# GSM_Shutter_lock_system.net
KiCad netlist of a schematic drawn in Altium Designer
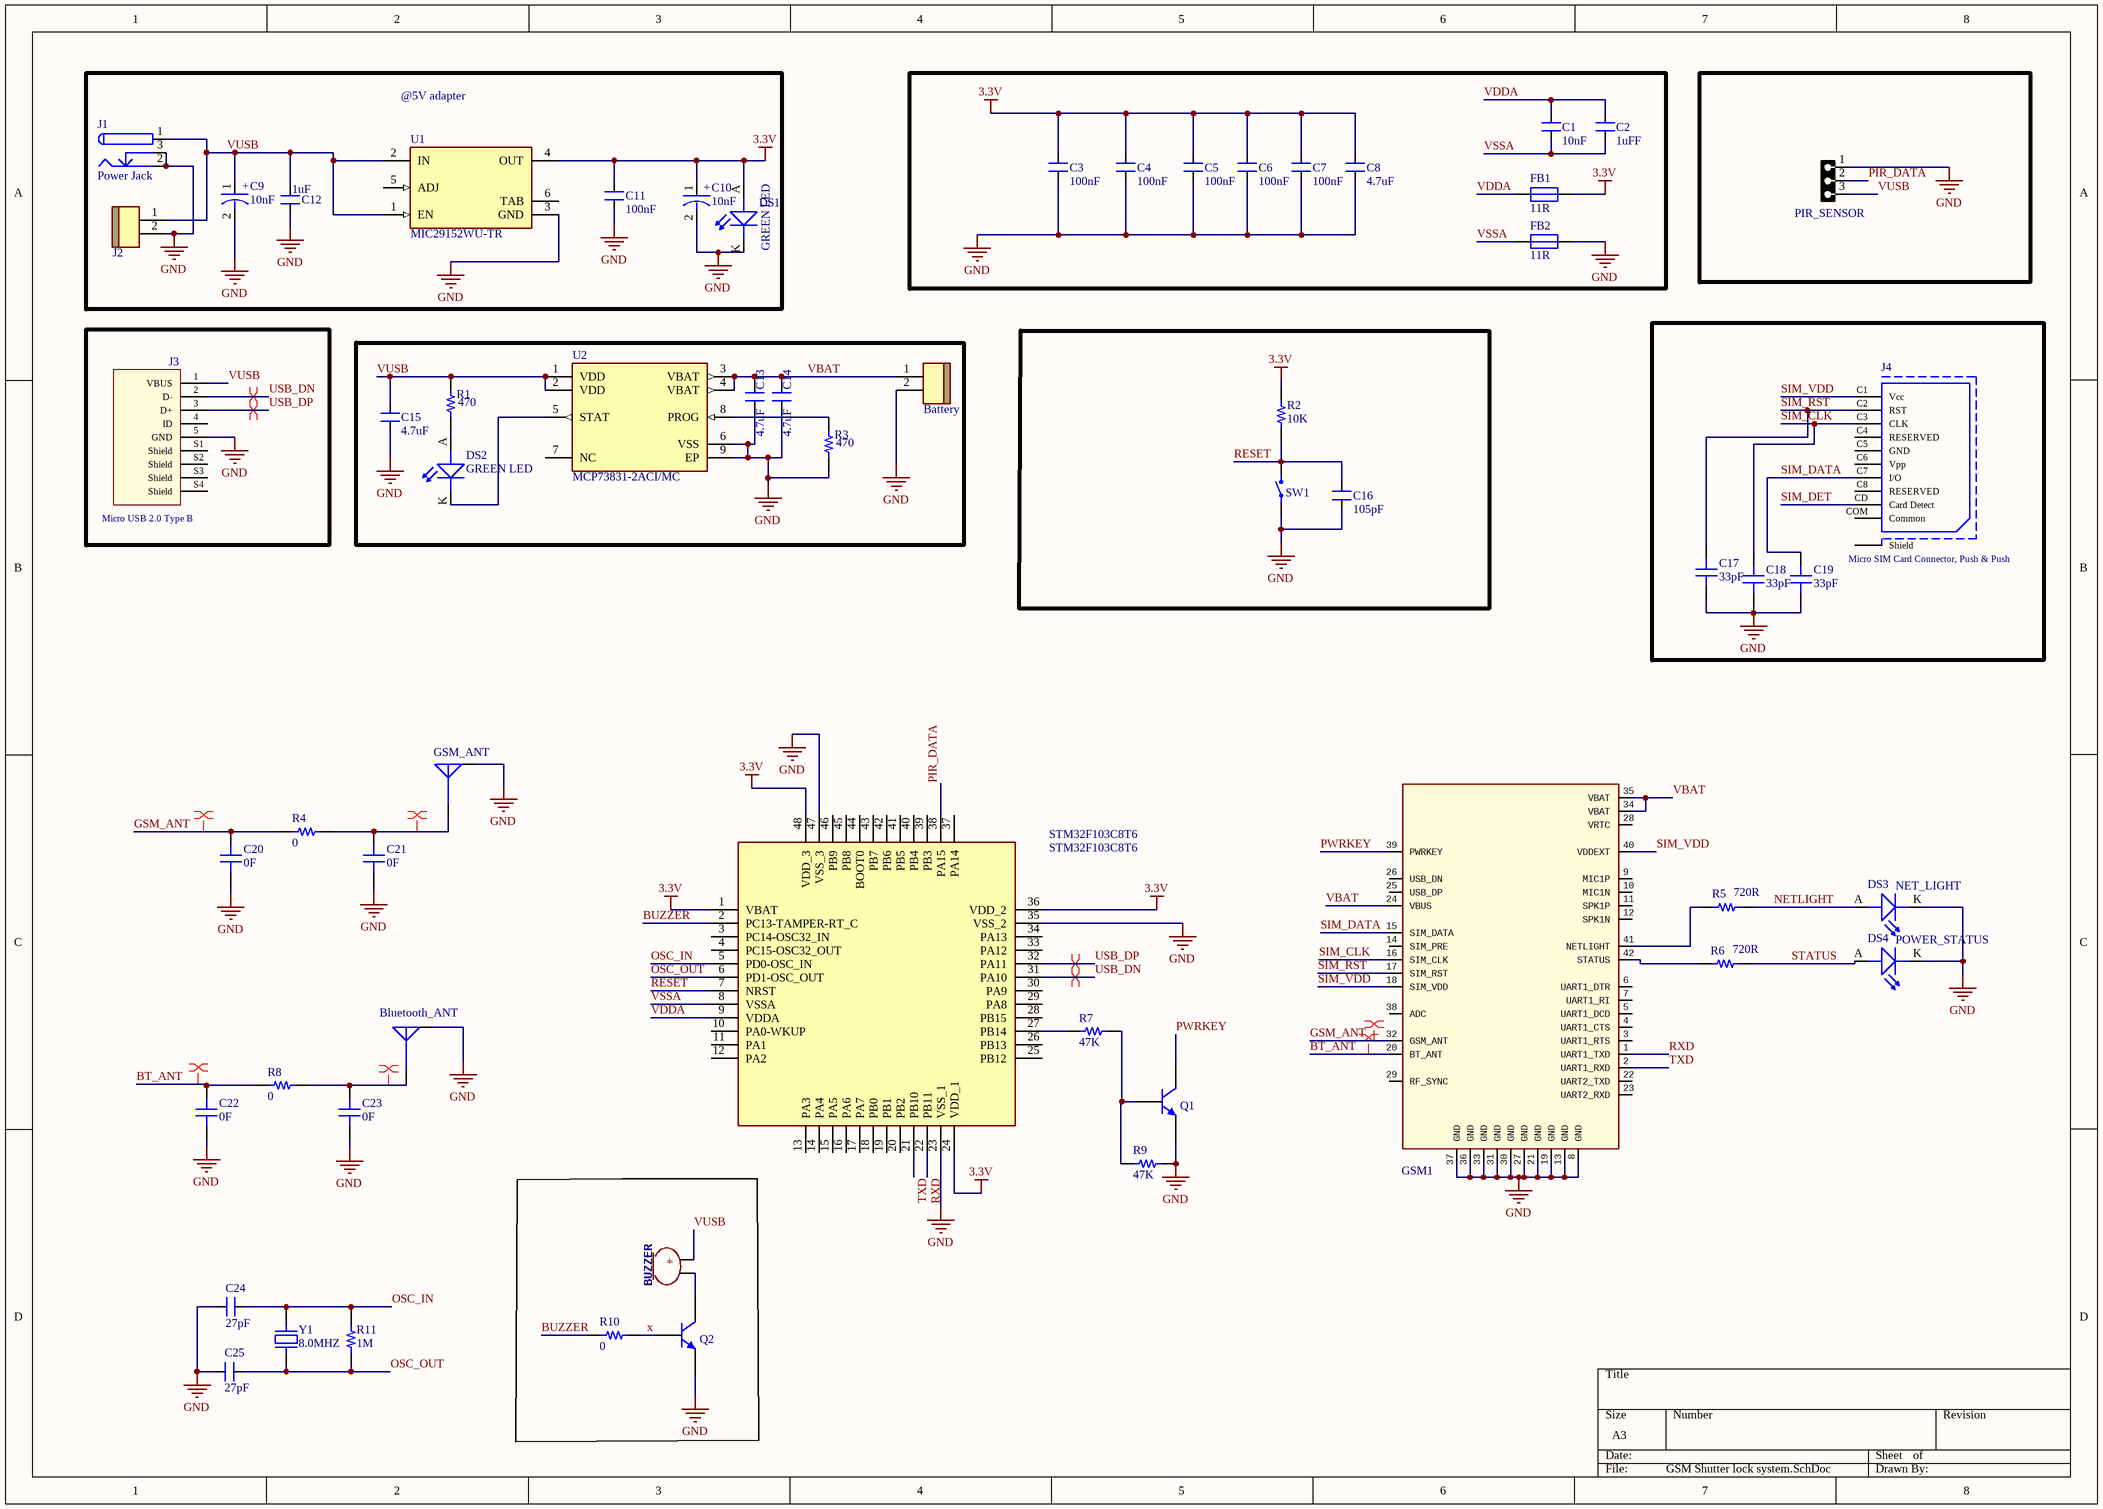
[diagram p0: GSM Shutter lock system.SchDoc]

(export (version "E")
  (design (tool "Eeschema 10.0.6"))
  (components
    (comp (ref "Battery")
      (value "JST BxB-PH-K 2Pin")
      (footprint "JST B2B-PH-K")
      (description "Connector Header Through Hole 0.079\" (2.00mm)")
      (fields (field (name "PARTNUMBER") "B2B-PH-K-S(LF)(SN)"))
      (libsource (lib "") (part "JST BxB-PH-K 2Pin_1"))
    )
    (comp (ref "Bluetooth_ANT")
      (value "UFL")
      (footprint "MOLEX SD-734120110")
      (fields (field (name "PARTNUMBER") "MOLEX SD-734120110"))
      (libsource (lib "Conn RF") (part "UFL MOLEX SD-734120110"))
    )
    (comp (ref "BUZZER")
      (value "MK")
      (footprint "MIC-9.7MM-TALL")
      (description "30Hz ~ 15kHz Analog Microphone Electret Condenser 2V ~ 10V Omnidirectional (-42dB ±3dB) PC Pins")
      (fields (field (name "PARTNUMBER") "POM-3542P-R"))
      (libsource (lib "Buzzer Microphone") (part "MIC 6.0mm H3.7mm (THD)"))
    )
    (comp (ref "C1")
      (value "10nF")
      (footprint "CAP_0805")
      (description "100pF ±5% 50V Ceramic Capacitor C0G, NP0 0805 (2012 Metric)")
      (fields
        (field (name "MANUFACTURER") "KEMET")
        (field (name "MANUFACTURER PART NUMBER") "CC0805JRNPO9BN101")
      )
      (libsource (lib "ESTEEMPCBLIB") (part "CAP_100pF-50V-5%-0805"))
    )
    (comp (ref "C2")
      (value "1uFF")
      (footprint "CAP_0805")
      (description "100pF ±5% 50V Ceramic Capacitor C0G, NP0 0805 (2012 Metric)")
      (fields
        (field (name "MANUFACTURER") "KEMET")
        (field (name "MANUFACTURER PART NUMBER") "CC0805JRNPO9BN101")
      )
      (libsource (lib "ESTEEMPCBLIB") (part "CAP_100pF-50V-5%-0805"))
    )
    (comp (ref "C3")
      (value "100nF")
      (footprint "CAP_0805")
      (description "100pF ±5% 50V Ceramic Capacitor C0G, NP0 0805 (2012 Metric)")
      (fields
        (field (name "MANUFACTURER") "KEMET")
        (field (name "MANUFACTURER PART NUMBER") "CC0805JRNPO9BN101")
      )
      (libsource (lib "ESTEEMPCBLIB") (part "CAP_100pF-50V-5%-0805"))
    )
    (comp (ref "C4")
      (value "100nF")
      (footprint "CAP_0805")
      (description "100pF ±5% 50V Ceramic Capacitor C0G, NP0 0805 (2012 Metric)")
      (fields
        (field (name "MANUFACTURER") "KEMET")
        (field (name "MANUFACTURER PART NUMBER") "CC0805JRNPO9BN101")
      )
      (libsource (lib "ESTEEMPCBLIB") (part "CAP_100pF-50V-5%-0805"))
    )
    (comp (ref "C5")
      (value "100nF")
      (footprint "CAP_0805")
      (description "100pF ±5% 50V Ceramic Capacitor C0G, NP0 0805 (2012 Metric)")
      (fields
        (field (name "MANUFACTURER") "KEMET")
        (field (name "MANUFACTURER PART NUMBER") "CC0805JRNPO9BN101")
      )
      (libsource (lib "ESTEEMPCBLIB") (part "CAP_100pF-50V-5%-0805"))
    )
    (comp (ref "C6")
      (value "100nF")
      (footprint "CAP_0805")
      (description "100pF ±5% 50V Ceramic Capacitor C0G, NP0 0805 (2012 Metric)")
      (fields
        (field (name "MANUFACTURER") "KEMET")
        (field (name "MANUFACTURER PART NUMBER") "CC0805JRNPO9BN101")
      )
      (libsource (lib "ESTEEMPCBLIB") (part "CAP_100pF-50V-5%-0805"))
    )
    (comp (ref "C7")
      (value "100nF")
      (footprint "CAP_0805")
      (description "100pF ±5% 50V Ceramic Capacitor C0G, NP0 0805 (2012 Metric)")
      (fields
        (field (name "MANUFACTURER") "KEMET")
        (field (name "MANUFACTURER PART NUMBER") "CC0805JRNPO9BN101")
      )
      (libsource (lib "ESTEEMPCBLIB") (part "CAP_100pF-50V-5%-0805"))
    )
    (comp (ref "C8")
      (value "4.7uF")
      (footprint "CAP_0805")
      (description "100pF ±5% 50V Ceramic Capacitor C0G, NP0 0805 (2012 Metric)")
      (fields
        (field (name "MANUFACTURER") "KEMET")
        (field (name "MANUFACTURER PART NUMBER") "CC0805JRNPO9BN101")
      )
      (libsource (lib "ESTEEMPCBLIB") (part "CAP_100pF-50V-5%-0805"))
    )
    (comp (ref "C9")
      (value "10nF")
      (footprint "ACAP_P339_D393_H531_RAD")
      (description "10µF 400V Aluminum Electrolytic Capacitors Radial, Can - SMD 10000 Hrs @ 105°C")
      (fields
        (field (name "MANUFACTURER") "Nichicon")
        (field (name "MANUFACTURER PART NUMBER") "ULV2G100MNL1GS")
      )
      (libsource (lib "ESTEEMPCBLIB") (part "CAP-P_10uF-400V-20%-RAD"))
    )
    (comp (ref "C10")
      (value "10nF")
      (footprint "ACAP_P339_D393_H531_RAD")
      (description "10µF 400V Aluminum Electrolytic Capacitors Radial, Can - SMD 10000 Hrs @ 105°C")
      (fields
        (field (name "MANUFACTURER") "Nichicon")
        (field (name "MANUFACTURER PART NUMBER") "ULV2G100MNL1GS")
      )
      (libsource (lib "ESTEEMPCBLIB") (part "CAP-P_10uF-400V-20%-RAD"))
    )
    (comp (ref "C11")
      (value "100nF")
      (footprint "CAP_0805")
      (description "100pF ±5% 50V Ceramic Capacitor C0G, NP0 0805 (2012 Metric)")
      (fields
        (field (name "MANUFACTURER") "KEMET")
        (field (name "MANUFACTURER PART NUMBER") "CC0805JRNPO9BN101")
      )
      (libsource (lib "ESTEEMPCBLIB") (part "CAP_100pF-50V-5%-0805"))
    )
    (comp (ref "C12")
      (value "1uF")
      (footprint "CAP_0805")
      (description "100pF ±5% 50V Ceramic Capacitor C0G, NP0 0805 (2012 Metric)")
      (fields
        (field (name "MANUFACTURER") "KEMET")
        (field (name "MANUFACTURER PART NUMBER") "CC0805JRNPO9BN101")
      )
      (libsource (lib "ESTEEMPCBLIB") (part "CAP_100pF-50V-5%-0805"))
    )
    (comp (ref "C13")
      (value "4.7uF")
      (footprint "CAP_0805")
      (description "100pF ±5% 50V Ceramic Capacitor C0G, NP0 0805 (2012 Metric)")
      (fields
        (field (name "MANUFACTURER") "KEMET")
        (field (name "MANUFACTURER PART NUMBER") "CC0805JRNPO9BN101")
      )
      (libsource (lib "ESTEEMPCBLIB") (part "CAP_100pF-50V-5%-0805"))
    )
    (comp (ref "C14")
      (value "4.7uF")
      (footprint "CAP_0805")
      (description "100pF ±5% 50V Ceramic Capacitor C0G, NP0 0805 (2012 Metric)")
      (fields
        (field (name "MANUFACTURER") "KEMET")
        (field (name "MANUFACTURER PART NUMBER") "CC0805JRNPO9BN101")
      )
      (libsource (lib "ESTEEMPCBLIB") (part "CAP_100pF-50V-5%-0805"))
    )
    (comp (ref "C15")
      (value "4.7uF")
      (footprint "CAP_0805")
      (description "100pF ±5% 50V Ceramic Capacitor C0G, NP0 0805 (2012 Metric)")
      (fields
        (field (name "MANUFACTURER") "KEMET")
        (field (name "MANUFACTURER PART NUMBER") "CC0805JRNPO9BN101")
      )
      (libsource (lib "ESTEEMPCBLIB") (part "CAP_100pF-50V-5%-0805"))
    )
    (comp (ref "C16")
      (value "105pF")
      (footprint "CAP_0805")
      (description "100pF ±5% 50V Ceramic Capacitor C0G, NP0 0805 (2012 Metric)")
      (fields
        (field (name "MANUFACTURER") "KEMET")
        (field (name "MANUFACTURER PART NUMBER") "CC0805JRNPO9BN101")
      )
      (libsource (lib "ESTEEMPCBLIB") (part "CAP_100pF-50V-5%-0805"))
    )
    (comp (ref "C17")
      (value "33pF")
      (footprint "CAP 0603_1608")
      (description "SMT Capacitor")
      (libsource (lib "Capacitor") (part "Cap 0603"))
    )
    (comp (ref "C18")
      (value "33pF")
      (footprint "CAP 0603_1608")
      (description "SMT Capacitor")
      (libsource (lib "Capacitor") (part "Cap 0603"))
    )
    (comp (ref "C19")
      (value "33pF")
      (footprint "CAP 0603_1608")
      (description "SMT Capacitor")
      (libsource (lib "Capacitor") (part "Cap 0603"))
    )
    (comp (ref "C20")
      (value "0F")
      (footprint "CAP 0402_1005")
      (description "SMT Capacitor")
      (libsource (lib "Capacitor") (part "Cap 0402"))
    )
    (comp (ref "C21")
      (value "0F")
      (footprint "CAP 0402_1005")
      (description "SMT Capacitor")
      (libsource (lib "Capacitor") (part "Cap 0402"))
    )
    (comp (ref "C22")
      (value "0F")
      (footprint "CAP 0402_1005")
      (description "SMT Capacitor")
      (libsource (lib "Capacitor") (part "Cap 0402"))
    )
    (comp (ref "C23")
      (value "0F")
      (footprint "CAP 0402_1005")
      (description "SMT Capacitor")
      (libsource (lib "Capacitor") (part "Cap 0402"))
    )
    (comp (ref "C24")
      (value "27pF")
      (footprint "CAP_0805")
      (description "100pF ±5% 50V Ceramic Capacitor C0G, NP0 0805 (2012 Metric)")
      (fields
        (field (name "MANUFACTURER") "KEMET")
        (field (name "MANUFACTURER PART NUMBER") "CC0805JRNPO9BN101")
      )
      (libsource (lib "ESTEEMPCBLIB") (part "CAP_100pF-50V-5%-0805"))
    )
    (comp (ref "C25")
      (value "27pF")
      (footprint "CAP_0805")
      (description "100pF ±5% 50V Ceramic Capacitor C0G, NP0 0805 (2012 Metric)")
      (fields
        (field (name "MANUFACTURER") "KEMET")
        (field (name "MANUFACTURER PART NUMBER") "CC0805JRNPO9BN101")
      )
      (libsource (lib "ESTEEMPCBLIB") (part "CAP_100pF-50V-5%-0805"))
    )
    (comp (ref "DS1")
      (value "GREEN LED")
      (footprint "LED_0805")
      (description "Green 569nm LED Indication - Discrete 2.1V 0805 (2012 Metric)")
      (fields
        (field (name "MANUFACTURER") "Vishay Lite-On")
        (field (name "MANUFACTURER PART NUMBER") "LTST-C171GKT")
      )
      (libsource (lib "ESTEEMPCBLIB") (part "LED_GREEN-2.2-20mA-0805"))
    )
    (comp (ref "DS2")
      (value "GREEN LED")
      (footprint "LED_0805")
      (description "Green 569nm LED Indication - Discrete 2.1V 0805 (2012 Metric)")
      (fields
        (field (name "MANUFACTURER") "Vishay Lite-On")
        (field (name "MANUFACTURER PART NUMBER") "LTST-C171GKT")
      )
      (libsource (lib "ESTEEMPCBLIB") (part "LED_GREEN-2.2-20mA-0805"))
    )
    (comp (ref "DS3")
      (value "NET_LIGHT")
      (footprint "LED_0805")
      (description "Blue 470nm LED Indication - Discrete 3.3V 0805 (2012 Metric)")
      (fields
        (field (name "MANUFACTURER") "Vishay Lite-On")
        (field (name "MANUFACTURER PART NUMBER") "LTST-C171TBKT")
      )
      (libsource (lib "ESTEEMPCBLIB") (part "LED_BLUE-3V3-20mA-0805"))
    )
    (comp (ref "DS4")
      (value "POWER_STATUS")
      (footprint "LED_0805")
      (description "Green 569nm LED Indication - Discrete 2.1V 0805 (2012 Metric)")
      (fields
        (field (name "MANUFACTURER") "Vishay Lite-On")
        (field (name "MANUFACTURER PART NUMBER") "LTST-C171GKT")
      )
      (libsource (lib "ESTEEMPCBLIB") (part "LED_GREEN-2.2-20mA-0805"))
    )
    (comp (ref "FB1")
      (value "11R")
      (footprint "IND_0805")
      (description "11 Ohms @ 100MHz 1 Power Line Ferrite Bead 0805 (2012 Metric) 1.5A 60mOhm")
      (fields
        (field (name "MANUFACTURER") "Murata")
        (field (name "MANUFACTURER PART NUMBER") "MI0805K110R-10")
      )
      (libsource (lib "ESTEEMPCBLIB") (part "FB_11R-100MHZ-1.5A-0805"))
    )
    (comp (ref "FB2")
      (value "11R")
      (footprint "IND_0805")
      (description "11 Ohms @ 100MHz 1 Power Line Ferrite Bead 0805 (2012 Metric) 1.5A 60mOhm")
      (fields
        (field (name "MANUFACTURER") "Murata")
        (field (name "MANUFACTURER PART NUMBER") "MI0805K110R-10")
      )
      (libsource (lib "ESTEEMPCBLIB") (part "FB_11R-100MHZ-1.5A-0805"))
    )
    (comp (ref "GSM1") (value "SIM800C") (footprint "Sim800C") (libsource (lib "Module") (part "SIM800C")))
    (comp (ref "GSM_ANT")
      (value "UFL")
      (footprint "MOLEX SD-734120110")
      (fields (field (name "PARTNUMBER") "MOLEX SD-734120110"))
      (libsource (lib "Conn RF") (part "UFL MOLEX SD-734120110"))
    )
    (comp (ref "J1")
      (value "Power Jack")
      (footprint "DC005")
      (fields (field (name "PARTNUMBER") "DC005-5.5MM"))
      (libsource (lib "Conn Jack") (part "Power Jack"))
    )
    (comp (ref "J2")
      (value "JST BxB-PH-K 2Pin")
      (footprint "JST B2B-PH-K")
      (description "Connector Header Through Hole 0.079\" (2.00mm)")
      (fields (field (name "PARTNUMBER") "B2B-PH-K-S(LF)(SN)"))
      (libsource (lib "Conn Terminal") (part "JST BxB-PH-K 2Pin"))
    )
    (comp (ref "J3")
      (value "Micro USB 2.0 Type B")
      (footprint "629105150521")
      (description "Micro USB 2.0 Type B Horizontal SMT 5 Contacts High Current WR-COM")
      (fields (field (name "PARTNUMBER") "629105150521") (field (name "PUBLISHER") "Wurth Elektronik"))
      (libsource (lib "Conn Usb") (part "Micro USB 2.0 Type B Horizontal (SMD) 629105150521"))
    )
    (comp (ref "J4")
      (value "Micro SIM Card Connector, Push & Push")
      (footprint "693021010811")
      (description "WR-CRD Micro SIM Card Connector, Push & Push, with Card Detection")
      (fields (field (name "PARTNUMBER") "693021010811") (field (name "PUBLISHER") "Wurth Elektronik"))
      (libsource (lib "Conn Card") (part "Micro SIM Card 693021010811"))
    )
    (comp (ref "PIR_SENSOR")
      (value "HDRF3")
      (footprint "HDRLP_F_1X3")
      (description "CONN, HEADER, Male, pitch: 2.54mm, 3POS")
      (libsource (lib "Conn Header") (part "HDRLP_F_1X3"))
    )
    (comp (ref "Q1")
      (value "8050")
      (footprint "SOT-23-3 2.9X2.4MM P0.95MM")
      (description "Bipolar (BJT) Transistor NPN 25V 1.5A 100MHz 625mW Surface Mount SOT-23")
      (fields (field (name "PARTNUMBER") "MMSS8050-L-TP"))
      (libsource (lib "Transistor") (part "MMSS8050 (SMD)"))
    )
    (comp (ref "Q2")
      (value "8050")
      (footprint "SOT-23-3 2.9X2.4MM P0.95MM")
      (description "Bipolar (BJT) Transistor NPN 25V 1.5A 100MHz 625mW Surface Mount SOT-23")
      (fields (field (name "PARTNUMBER") "MMSS8050-L-TP"))
      (libsource (lib "Transistor") (part "MMSS8050 (SMD)"))
    )
    (comp (ref "R1")
      (value "470")
      (footprint "RES 0603_1608")
      (description "SMT Resistor")
      (libsource (lib "Resistor") (part "Res 0603"))
    )
    (comp (ref "R2")
      (value "10K")
      (footprint "RES 0603_1608")
      (description "SMT Resistor")
      (libsource (lib "Resistor") (part "Res 0603"))
    )
    (comp (ref "R3")
      (value "470")
      (footprint "RES 0603_1608")
      (description "SMT Resistor")
      (libsource (lib "Resistor") (part "Res 0603"))
    )
    (comp (ref "R4")
      (value "0")
      (footprint "RES 0402_1005")
      (description "SMT Resistor")
      (libsource (lib "Resistor") (part "Res 0402"))
    )
    (comp (ref "R5")
      (value "720R")
      (footprint "RES 0603_1608")
      (description "SMT Resistor")
      (libsource (lib "Resistor") (part "Res 0603"))
    )
    (comp (ref "R6")
      (value "720R")
      (footprint "RES 0603_1608")
      (description "SMT Resistor")
      (libsource (lib "Resistor") (part "Res 0603"))
    )
    (comp (ref "R7")
      (value "47K")
      (footprint "RES 0603_1608")
      (description "SMT Resistor")
      (libsource (lib "Resistor") (part "Res 0603"))
    )
    (comp (ref "R8")
      (value "0")
      (footprint "RES 0402_1005")
      (description "SMT Resistor")
      (libsource (lib "Resistor") (part "Res 0402"))
    )
    (comp (ref "R9")
      (value "47K")
      (footprint "RES 0603_1608")
      (description "SMT Resistor")
      (libsource (lib "Resistor") (part "Res 0603"))
    )
    (comp (ref "R10")
      (value "0")
      (footprint "RES 0402_1005")
      (description "SMT Resistor")
      (libsource (lib "Resistor") (part "Res 0402"))
    )
    (comp (ref "R11")
      (value "1M")
      (footprint "RES 0603_1608")
      (description "SMT Resistor")
      (libsource (lib "Resistor") (part "Res 0603"))
    )
    (comp (ref "STM32F103C8T6")
      (value "STM32F103C8T6")
      (footprint "LQFP-48_19.6_393_58X11_SMD")
      (description "ARM® Cortex®-M3 STM32F1 Microcontroller IC 32-Bit 72MHz 64KB (64K x 8) FLASH 48-LQFP (7x7)")
      (fields (field (name "MANUFACTURER") "STMicroelectronics"))
      (libsource (lib "ESTEEMPCBLIB") (part "IC_STM32F103C8T6"))
    )
    (comp (ref "SW1")
      (value "Tactile 2PIN 6X3.5mm H4.57mm (SMD)")
      (footprint "SWPBS_SPST_6X3X5")
      (description "Tactile Switch SPST-NO Top Actuated Surface Mount")
      (fields (field (name "PARTNUMBER") "FSMSMTR-ND"))
      (libsource (lib "Switch") (part "Tactile 2PIN 6X3.5mm H4.57mm (SMD)"))
    )
    (comp (ref "U1")
      (value "MIC29152WU-TR")
      (footprint "FP-C04-012-MFG")
      (description "IC REG LIN POS ADJ 1.5A TO263-5")
      (libsource (lib "Altium Content Vault") (part "1a6b915b87719d97fe3e21ac07cc413"))
    )
    (comp (ref "U2")
      (value "MCP73831-2ACI/MC")
      (footprint "FP-C04-123-MFG")
      (description "IC CONTROLLER LI-ION 4.2V 8DFN")
      (fields
        (field (name "OCTOPART") "https://octopart.com/mcp73831-2aci%2Fmc-microchip-16517355")
        (field (name "MANUFACTURER") "Microchip")
      )
      (libsource (lib "Altium Content Vault") (part "ff4aef3c73132f256b0e29225c28959"))
    )
    (comp (ref "Y1")
      (value "8.0MHZ")
      (footprint "HC-49S SMD")
      (description "SMT Crystal")
      (libsource (lib "Xtal") (part "Crystal HC-49S SMD"))
    )
  )
  (nets
    (net (code "1") (name "/BT_ANT") (class "Default")
      (node (ref "C22") (pin "2") (pinfunction "2_2") (pintype "passive"))
      (node (ref "GSM1") (pin "20") (pinfunction "BT_ANT_20") (pintype "passive"))
      (node (ref "R8") (pin "1") (pinfunction "1_1") (pintype "passive"))
    )
    (net (code "2") (name "/BUZZER") (class "Default")
      (node (ref "R10") (pin "1") (pinfunction "1_1") (pintype "passive"))
      (node (ref "STM32F103C8T6") (pin "2") (pinfunction "PC13-TAMPER-RT_C_2") (pintype "passive"))
    )
    (net (code "3") (name "/GSM_ANT") (class "Default")
      (node (ref "C20") (pin "2") (pinfunction "2_2") (pintype "passive"))
      (node (ref "GSM1") (pin "32") (pinfunction "GSM_ANT_32") (pintype "passive"))
      (node (ref "R4") (pin "1") (pinfunction "1_1") (pintype "passive"))
    )
    (net (code "4") (name "/NETLIGHT") (class "Default")
      (node (ref "DS3") (pin "A") (pinfunction "ANODE_A") (pintype "passive"))
      (node (ref "R5") (pin "2") (pinfunction "2_2") (pintype "passive"))
    )
    (net (code "5") (name "/OSC_IN") (class "Default")
      (node (ref "C24") (pin "1") (pinfunction "1_1") (pintype "passive"))
      (node (ref "R11") (pin "2") (pinfunction "2_2") (pintype "passive"))
      (node (ref "STM32F103C8T6") (pin "5") (pinfunction "PD0-OSC_IN_5") (pintype "passive"))
      (node (ref "Y1") (pin "2") (pinfunction "2_2") (pintype "passive"))
    )
    (net (code "6") (name "/OSC_OUT") (class "Default")
      (node (ref "C25") (pin "1") (pinfunction "1_1") (pintype "passive"))
      (node (ref "R11") (pin "1") (pinfunction "1_1") (pintype "passive"))
      (node (ref "STM32F103C8T6") (pin "6") (pinfunction "PD1-OSC_OUT_6") (pintype "passive"))
      (node (ref "Y1") (pin "1") (pinfunction "1_1") (pintype "passive"))
    )
    (net (code "7") (name "/PIR_DATA") (class "Default")
      (node (ref "PIR_SENSOR") (pin "2") (pinfunction "2_2") (pintype "passive"))
      (node (ref "STM32F103C8T6") (pin "38") (pinfunction "PA15_38") (pintype "passive"))
    )
    (net (code "8") (name "/PWRKEY") (class "Default")
      (node (ref "GSM1") (pin "39") (pinfunction "PWRKEY_39") (pintype "passive"))
      (node (ref "Q1") (pin "3") (pinfunction "C_3") (pintype "passive"))
    )
    (net (code "9") (name "/RESET") (class "Default")
      (node (ref "C16") (pin "2") (pinfunction "2_2") (pintype "passive"))
      (node (ref "R2") (pin "1") (pinfunction "1_1") (pintype "passive"))
      (node (ref "STM32F103C8T6") (pin "7") (pinfunction "NRST_7") (pintype "passive"))
      (node (ref "SW1") (pin "2") (pinfunction "2_2") (pintype "passive"))
    )
    (net (code "10") (name "/RXD") (class "Default")
      (node (ref "GSM1") (pin "1") (pinfunction "UART1_TXD_1") (pintype "passive"))
      (node (ref "STM32F103C8T6") (pin "22") (pinfunction "PB11_22") (pintype "passive"))
    )
    (net (code "11") (name "/SIM_CLK") (class "Default")
      (node (ref "C18") (pin "2") (pinfunction "2_2") (pintype "passive"))
      (node (ref "GSM1") (pin "16") (pinfunction "SIM_CLK_16") (pintype "passive"))
      (node (ref "J4") (pin "C3") (pinfunction "CLK_C3") (pintype "passive"))
    )
    (net (code "12") (name "/SIM_DATA") (class "Default")
      (node (ref "C19") (pin "2") (pinfunction "2_2") (pintype "passive"))
      (node (ref "GSM1") (pin "15") (pinfunction "SIM_DATA_15") (pintype "passive"))
      (node (ref "J4") (pin "C7") (pinfunction "I/O_C7") (pintype "passive"))
    )
    (net (code "13") (name "/SIM_DET") (class "Default")
      (node (ref "J4") (pin "CD") (pinfunction "Card_Detect_CD") (pintype "passive"))
    )
    (net (code "14") (name "/SIM_RST") (class "Default")
      (node (ref "C17") (pin "2") (pinfunction "2_2") (pintype "passive"))
      (node (ref "GSM1") (pin "17") (pinfunction "SIM_RST_17") (pintype "passive"))
      (node (ref "J4") (pin "C2") (pinfunction "RST_C2") (pintype "passive"))
    )
    (net (code "15") (name "/SIM_VDD") (class "Default")
      (node (ref "GSM1") (pin "18") (pinfunction "SIM_VDD_18") (pintype "passive"))
      (node (ref "GSM1") (pin "40") (pinfunction "VDDEXT_40") (pintype "passive"))
      (node (ref "J4") (pin "C1") (pinfunction "Vcc_C1") (pintype "passive"))
    )
    (net (code "16") (name "/STATUS") (class "Default")
      (node (ref "DS4") (pin "A") (pinfunction "ANODE_A") (pintype "passive"))
      (node (ref "R6") (pin "2") (pinfunction "2_2") (pintype "passive"))
    )
    (net (code "17") (name "/TXD") (class "Default")
      (node (ref "GSM1") (pin "2") (pinfunction "UART1_RXD_2") (pintype "passive"))
      (node (ref "STM32F103C8T6") (pin "21") (pinfunction "PB10_21") (pintype "passive"))
    )
    (net (code "18") (name "/USB_DN") (class "Default")
      (node (ref "J3") (pin "2") (pinfunction "D-_2") (pintype "passive"))
      (node (ref "STM32F103C8T6") (pin "31") (pinfunction "PA10_31") (pintype "passive"))
    )
    (net (code "19") (name "/USB_DP") (class "Default")
      (node (ref "J3") (pin "3") (pinfunction "D+_3") (pintype "passive"))
      (node (ref "STM32F103C8T6") (pin "32") (pinfunction "PA11_32") (pintype "passive"))
    )
    (net (code "20") (name "/VBAT") (class "Default")
      (node (ref "Battery") (pin "1") (pinfunction "1_1") (pintype "passive"))
      (node (ref "C13") (pin "2") (pinfunction "2_2") (pintype "passive"))
      (node (ref "C14") (pin "2") (pinfunction "2_2") (pintype "passive"))
      (node (ref "GSM1") (pin "24") (pinfunction "VBUS_24") (pintype "passive"))
      (node (ref "GSM1") (pin "34") (pinfunction "VBAT_34") (pintype "passive"))
      (node (ref "GSM1") (pin "35") (pinfunction "VBAT_35") (pintype "passive"))
      (node (ref "U2") (pin "3") (pinfunction "VBAT_3") (pintype "output"))
      (node (ref "U2") (pin "4") (pinfunction "VBAT_4") (pintype "output"))
    )
    (net (code "21") (name "/VDDA") (class "Default")
      (node (ref "C1") (pin "2") (pinfunction "2_2") (pintype "passive"))
      (node (ref "C2") (pin "2") (pinfunction "2_2") (pintype "passive"))
      (node (ref "FB1") (pin "1") (pinfunction "1_1") (pintype "passive"))
      (node (ref "STM32F103C8T6") (pin "9") (pinfunction "VDDA_9") (pintype "passive"))
    )
    (net (code "22") (name "/VSSA") (class "Default")
      (node (ref "C1") (pin "1") (pinfunction "1_1") (pintype "passive"))
      (node (ref "C2") (pin "1") (pinfunction "1_1") (pintype "passive"))
      (node (ref "FB2") (pin "1") (pinfunction "1_1") (pintype "passive"))
      (node (ref "STM32F103C8T6") (pin "8") (pinfunction "VSSA_8") (pintype "passive"))
    )
    (net (code "23") (name "/VUSB") (class "Default")
      (node (ref "BUZZER") (pin "2") (pinfunction "OUT_2") (pintype "passive"))
      (node (ref "C12") (pin "2") (pinfunction "2_2") (pintype "passive"))
      (node (ref "C15") (pin "2") (pinfunction "2_2") (pintype "passive"))
      (node (ref "C9") (pin "1") (pinfunction "1_1") (pintype "passive"))
      (node (ref "J1") (pin "1") (pinfunction "1_1") (pintype "power_in"))
      (node (ref "J2") (pin "1") (pinfunction "1_1") (pintype "passive"))
      (node (ref "J3") (pin "1") (pinfunction "VBUS_1") (pintype "passive"))
      (node (ref "PIR_SENSOR") (pin "3") (pinfunction "3_3") (pintype "passive"))
      (node (ref "R1") (pin "2") (pinfunction "2_2") (pintype "passive"))
      (node (ref "U1") (pin "1") (pinfunction "EN_1") (pintype "input"))
      (node (ref "U1") (pin "2") (pinfunction "IN_2") (pintype "power_in"))
      (node (ref "U2") (pin "1") (pinfunction "VDD_1") (pintype "power_in"))
      (node (ref "U2") (pin "2") (pinfunction "VDD_2") (pintype "power_in"))
    )
    (net (code "24") (name "/x") (class "Default")
      (node (ref "Q2") (pin "1") (pinfunction "B_1") (pintype "passive"))
      (node (ref "R10") (pin "2") (pinfunction "2_2") (pintype "passive"))
    )
    (net (code "25") (name "3.3V") (class "Default")
      (node (ref "C10") (pin "1") (pinfunction "1_1") (pintype "passive"))
      (node (ref "C11") (pin "2") (pinfunction "2_2") (pintype "passive"))
      (node (ref "C3") (pin "2") (pinfunction "2_2") (pintype "passive"))
      (node (ref "C4") (pin "2") (pinfunction "2_2") (pintype "passive"))
      (node (ref "C5") (pin "2") (pinfunction "2_2") (pintype "passive"))
      (node (ref "C6") (pin "2") (pinfunction "2_2") (pintype "passive"))
      (node (ref "C7") (pin "2") (pinfunction "2_2") (pintype "passive"))
      (node (ref "C8") (pin "2") (pinfunction "2_2") (pintype "passive"))
      (node (ref "DS1") (pin "A") (pinfunction "ANODE_A") (pintype "passive"))
      (node (ref "FB1") (pin "2") (pinfunction "2_2") (pintype "passive"))
      (node (ref "R2") (pin "2") (pinfunction "2_2") (pintype "passive"))
      (node (ref "STM32F103C8T6") (pin "1") (pinfunction "VBAT_1") (pintype "passive"))
      (node (ref "STM32F103C8T6") (pin "24") (pinfunction "VDD_1_24") (pintype "passive"))
      (node (ref "STM32F103C8T6") (pin "36") (pinfunction "VDD_2_36") (pintype "passive"))
      (node (ref "STM32F103C8T6") (pin "48") (pinfunction "VDD_3_48") (pintype "passive"))
      (node (ref "U1") (pin "4") (pinfunction "OUT_4") (pintype "passive"))
    )
    (net (code "26") (name "GND") (class "Default")
      (node (ref "Battery") (pin "2") (pinfunction "2_2") (pintype "passive"))
      (node (ref "Bluetooth_ANT") (pin "G") (pinfunction "G_G") (pintype "passive"))
      (node (ref "C10") (pin "2") (pinfunction "2_2") (pintype "passive"))
      (node (ref "C11") (pin "1") (pinfunction "1_1") (pintype "passive"))
      (node (ref "C12") (pin "1") (pinfunction "1_1") (pintype "passive"))
      (node (ref "C13") (pin "1") (pinfunction "1_1") (pintype "passive"))
      (node (ref "C14") (pin "1") (pinfunction "1_1") (pintype "passive"))
      (node (ref "C15") (pin "1") (pinfunction "1_1") (pintype "passive"))
      (node (ref "C16") (pin "1") (pinfunction "1_1") (pintype "passive"))
      (node (ref "C17") (pin "1") (pinfunction "1_1") (pintype "passive"))
      (node (ref "C18") (pin "1") (pinfunction "1_1") (pintype "passive"))
      (node (ref "C19") (pin "1") (pinfunction "1_1") (pintype "passive"))
      (node (ref "C20") (pin "1") (pinfunction "1_1") (pintype "passive"))
      (node (ref "C21") (pin "1") (pinfunction "1_1") (pintype "passive"))
      (node (ref "C22") (pin "1") (pinfunction "1_1") (pintype "passive"))
      (node (ref "C23") (pin "1") (pinfunction "1_1") (pintype "passive"))
      (node (ref "C24") (pin "2") (pinfunction "2_2") (pintype "passive"))
      (node (ref "C25") (pin "2") (pinfunction "2_2") (pintype "passive"))
      (node (ref "C3") (pin "1") (pinfunction "1_1") (pintype "passive"))
      (node (ref "C4") (pin "1") (pinfunction "1_1") (pintype "passive"))
      (node (ref "C5") (pin "1") (pinfunction "1_1") (pintype "passive"))
      (node (ref "C6") (pin "1") (pinfunction "1_1") (pintype "passive"))
      (node (ref "C7") (pin "1") (pinfunction "1_1") (pintype "passive"))
      (node (ref "C8") (pin "1") (pinfunction "1_1") (pintype "passive"))
      (node (ref "C9") (pin "2") (pinfunction "2_2") (pintype "passive"))
      (node (ref "DS1") (pin "K") (pinfunction "CATHODE_K") (pintype "passive"))
      (node (ref "DS3") (pin "K") (pinfunction "CATHODE_K") (pintype "passive"))
      (node (ref "DS4") (pin "K") (pinfunction "CATHODE_K") (pintype "passive"))
      (node (ref "FB2") (pin "2") (pinfunction "2_2") (pintype "passive"))
      (node (ref "GSM1") (pin "13") (pinfunction "GND_13") (pintype "passive"))
      (node (ref "GSM1") (pin "19") (pinfunction "GND_19") (pintype "passive"))
      (node (ref "GSM1") (pin "21") (pinfunction "GND_21") (pintype "passive"))
      (node (ref "GSM1") (pin "27") (pinfunction "GND_27") (pintype "passive"))
      (node (ref "GSM1") (pin "30") (pinfunction "GND_30") (pintype "passive"))
      (node (ref "GSM1") (pin "31") (pinfunction "GND_31") (pintype "passive"))
      (node (ref "GSM1") (pin "33") (pinfunction "GND_33") (pintype "passive"))
      (node (ref "GSM1") (pin "36") (pinfunction "GND_36") (pintype "passive"))
      (node (ref "GSM1") (pin "37") (pinfunction "GND_37") (pintype "passive"))
      (node (ref "GSM1") (pin "8") (pinfunction "GND_8") (pintype "passive"))
      (node (ref "GSM_ANT") (pin "G") (pinfunction "G_G") (pintype "passive"))
      (node (ref "J1") (pin "2") (pinfunction "2_2") (pintype "power_in"))
      (node (ref "J1") (pin "3") (pinfunction "3_3") (pintype "power_in"))
      (node (ref "J2") (pin "2") (pinfunction "2_2") (pintype "passive"))
      (node (ref "J3") (pin "5") (pinfunction "GND_5") (pintype "passive"))
      (node (ref "PIR_SENSOR") (pin "1") (pinfunction "1_1") (pintype "passive"))
      (node (ref "Q1") (pin "2") (pinfunction "E_2") (pintype "passive"))
      (node (ref "Q2") (pin "2") (pinfunction "E_2") (pintype "passive"))
      (node (ref "R3") (pin "1") (pinfunction "1_1") (pintype "passive"))
      (node (ref "R9") (pin "1") (pinfunction "1_1") (pintype "passive"))
      (node (ref "STM32F103C8T6") (pin "23") (pinfunction "VSS_1_23") (pintype "passive"))
      (node (ref "STM32F103C8T6") (pin "35") (pinfunction "VSS_2_35") (pintype "passive"))
      (node (ref "STM32F103C8T6") (pin "47") (pinfunction "VSS_3_47") (pintype "passive"))
      (node (ref "SW1") (pin "1") (pinfunction "1_1") (pintype "passive"))
      (node (ref "U1") (pin "3") (pinfunction "GND_3") (pintype "power_in"))
      (node (ref "U2") (pin "6") (pinfunction "VSS_6") (pintype "power_in"))
      (node (ref "U2") (pin "9") (pinfunction "EP_9") (pintype "power_in"))
    )
    (net (code "27") (name "Net-(BUZZER-GND)") (class "Default")
      (node (ref "BUZZER") (pin "1") (pinfunction "GND_1") (pintype "passive"))
      (node (ref "Q2") (pin "3") (pinfunction "C_3") (pintype "passive"))
    )
    (net (code "28") (name "Net-(Bluetooth_ANT-PadS)") (class "Default")
      (node (ref "Bluetooth_ANT") (pin "S") (pinfunction "S_S") (pintype "passive"))
      (node (ref "C23") (pin "2") (pinfunction "2_2") (pintype "passive"))
      (node (ref "R8") (pin "2") (pinfunction "2_2") (pintype "passive"))
    )
    (net (code "29") (name "Net-(C21-Pad2)") (class "Default")
      (node (ref "C21") (pin "2") (pinfunction "2_2") (pintype "passive"))
      (node (ref "GSM_ANT") (pin "S") (pinfunction "S_S") (pintype "passive"))
      (node (ref "R4") (pin "2") (pinfunction "2_2") (pintype "passive"))
    )
    (net (code "30") (name "Net-(DS2-ANODE)") (class "Default")
      (node (ref "DS2") (pin "A") (pinfunction "ANODE_A") (pintype "passive"))
      (node (ref "R1") (pin "1") (pinfunction "1_1") (pintype "passive"))
    )
    (net (code "31") (name "Net-(DS2-CATHODE)") (class "Default")
      (node (ref "DS2") (pin "K") (pinfunction "CATHODE_K") (pintype "passive"))
      (node (ref "U2") (pin "5") (pinfunction "STAT_5") (pintype "output"))
    )
    (net (code "32") (name "Net-(GSM1-NETLIGHT)") (class "Default")
      (node (ref "GSM1") (pin "41") (pinfunction "NETLIGHT_41") (pintype "passive"))
      (node (ref "R5") (pin "1") (pinfunction "1_1") (pintype "passive"))
    )
    (net (code "33") (name "Net-(GSM1-STATUS)") (class "Default")
      (node (ref "GSM1") (pin "42") (pinfunction "STATUS_42") (pintype "passive"))
      (node (ref "R6") (pin "1") (pinfunction "1_1") (pintype "passive"))
    )
    (net (code "34") (name "Net-(Q1-B)") (class "Default")
      (node (ref "Q1") (pin "1") (pinfunction "B_1") (pintype "passive"))
      (node (ref "R7") (pin "1") (pinfunction "1_1") (pintype "passive"))
      (node (ref "R9") (pin "2") (pinfunction "2_2") (pintype "passive"))
    )
    (net (code "35") (name "Net-(STM32F103C8T6-PB14)") (class "Default")
      (node (ref "R7") (pin "2") (pinfunction "2_2") (pintype "passive"))
      (node (ref "STM32F103C8T6") (pin "27") (pinfunction "PB14_27") (pintype "passive"))
    )
    (net (code "36") (name "Net-(U2-PROG)") (class "Default")
      (node (ref "R3") (pin "2") (pinfunction "2_2") (pintype "passive"))
      (node (ref "U2") (pin "8") (pinfunction "PROG_8") (pintype "input"))
    )
    (net (code "37") (name "unconnected-(GSM1-ADC-Pad38)") (class "Default")
      (node (ref "GSM1") (pin "38") (pinfunction "ADC_38") (pintype "passive"))
    )
    (net (code "38") (name "unconnected-(GSM1-MIC1N-Pad10)") (class "Default")
      (node (ref "GSM1") (pin "10") (pinfunction "MIC1N_10") (pintype "passive"))
    )
    (net (code "39") (name "unconnected-(GSM1-MIC1P-Pad9)") (class "Default")
      (node (ref "GSM1") (pin "9") (pinfunction "MIC1P_9") (pintype "passive"))
    )
    (net (code "40") (name "unconnected-(GSM1-RF_SYNC-Pad29)") (class "Default")
      (node (ref "GSM1") (pin "29") (pinfunction "RF_SYNC_29") (pintype "passive"))
    )
    (net (code "41") (name "unconnected-(GSM1-SIM_PRE-Pad14)") (class "Default")
      (node (ref "GSM1") (pin "14") (pinfunction "SIM_PRE_14") (pintype "passive"))
    )
    (net (code "42") (name "unconnected-(GSM1-SPK1N-Pad12)") (class "Default")
      (node (ref "GSM1") (pin "12") (pinfunction "SPK1N_12") (pintype "passive"))
    )
    (net (code "43") (name "unconnected-(GSM1-SPK1P-Pad11)") (class "Default")
      (node (ref "GSM1") (pin "11") (pinfunction "SPK1P_11") (pintype "passive"))
    )
    (net (code "44") (name "unconnected-(GSM1-UART1_CTS-Pad4)") (class "Default")
      (node (ref "GSM1") (pin "4") (pinfunction "UART1_CTS_4") (pintype "passive"))
    )
    (net (code "45") (name "unconnected-(GSM1-UART1_DCD-Pad5)") (class "Default")
      (node (ref "GSM1") (pin "5") (pinfunction "UART1_DCD_5") (pintype "passive"))
    )
    (net (code "46") (name "unconnected-(GSM1-UART1_DTR-Pad6)") (class "Default")
      (node (ref "GSM1") (pin "6") (pinfunction "UART1_DTR_6") (pintype "passive"))
    )
    (net (code "47") (name "unconnected-(GSM1-UART1_RI-Pad7)") (class "Default")
      (node (ref "GSM1") (pin "7") (pinfunction "UART1_RI_7") (pintype "passive"))
    )
    (net (code "48") (name "unconnected-(GSM1-UART1_RTS-Pad3)") (class "Default")
      (node (ref "GSM1") (pin "3") (pinfunction "UART1_RTS_3") (pintype "passive"))
    )
    (net (code "49") (name "unconnected-(GSM1-UART2_RXD-Pad23)") (class "Default")
      (node (ref "GSM1") (pin "23") (pinfunction "UART2_RXD_23") (pintype "passive"))
    )
    (net (code "50") (name "unconnected-(GSM1-UART2_TXD-Pad22)") (class "Default")
      (node (ref "GSM1") (pin "22") (pinfunction "UART2_TXD_22") (pintype "passive"))
    )
    (net (code "51") (name "unconnected-(GSM1-USB_DN-Pad26)") (class "Default")
      (node (ref "GSM1") (pin "26") (pinfunction "USB_DN_26") (pintype "passive"))
    )
    (net (code "52") (name "unconnected-(GSM1-USB_DP-Pad25)") (class "Default")
      (node (ref "GSM1") (pin "25") (pinfunction "USB_DP_25") (pintype "passive"))
    )
    (net (code "53") (name "unconnected-(GSM1-VRTC-Pad28)") (class "Default")
      (node (ref "GSM1") (pin "28") (pinfunction "VRTC_28") (pintype "passive"))
    )
    (net (code "54") (name "unconnected-(J3-ID-Pad4)") (class "Default")
      (node (ref "J3") (pin "4") (pinfunction "ID_4") (pintype "passive"))
    )
    (net (code "55") (name "unconnected-(J3-Shield-PadS1)") (class "Default")
      (node (ref "J3") (pin "S1") (pinfunction "Shield_S1") (pintype "passive"))
    )
    (net (code "56") (name "unconnected-(J3-Shield-PadS2)") (class "Default")
      (node (ref "J3") (pin "S2") (pinfunction "Shield_S2") (pintype "passive"))
    )
    (net (code "57") (name "unconnected-(J3-Shield-PadS3)") (class "Default")
      (node (ref "J3") (pin "S3") (pinfunction "Shield_S3") (pintype "passive"))
    )
    (net (code "58") (name "unconnected-(J3-Shield-PadS4)") (class "Default")
      (node (ref "J3") (pin "S4") (pinfunction "Shield_S4") (pintype "passive"))
    )
    (net (code "59") (name "unconnected-(J4-Common-PadCOM)") (class "Default")
      (node (ref "J4") (pin "COM") (pinfunction "Common_COM") (pintype "passive"))
    )
    (net (code "60") (name "unconnected-(J4-GND-PadC5)") (class "Default")
      (node (ref "J4") (pin "C5") (pinfunction "GND_C5") (pintype "passive"))
    )
    (net (code "61") (name "unconnected-(J4-PadShield)") (class "Default")
      (node (ref "J4") (pin "Shield") (pinfunction "Shield_Shield") (pintype "passive"))
    )
    (net (code "62") (name "unconnected-(J4-RESERVED-PadC4)") (class "Default")
      (node (ref "J4") (pin "C4") (pinfunction "RESERVED_C4") (pintype "passive"))
    )
    (net (code "63") (name "unconnected-(J4-RESERVED-PadC8)") (class "Default")
      (node (ref "J4") (pin "C8") (pinfunction "RESERVED_C8") (pintype "passive"))
    )
    (net (code "64") (name "unconnected-(J4-Vpp-PadC6)") (class "Default")
      (node (ref "J4") (pin "C6") (pinfunction "Vpp_C6") (pintype "passive"))
    )
    (net (code "65") (name "unconnected-(STM32F103C8T6-BOOT0-Pad44)") (class "Default")
      (node (ref "STM32F103C8T6") (pin "44") (pinfunction "BOOT0_44") (pintype "passive"))
    )
    (net (code "66") (name "unconnected-(STM32F103C8T6-PA0-WKUP-Pad10)") (class "Default")
      (node (ref "STM32F103C8T6") (pin "10") (pinfunction "PA0-WKUP_10") (pintype "passive"))
    )
    (net (code "67") (name "unconnected-(STM32F103C8T6-PA1-Pad11)") (class "Default")
      (node (ref "STM32F103C8T6") (pin "11") (pinfunction "PA1_11") (pintype "passive"))
    )
    (net (code "68") (name "unconnected-(STM32F103C8T6-PA2-Pad12)") (class "Default")
      (node (ref "STM32F103C8T6") (pin "12") (pinfunction "PA2_12") (pintype "passive"))
    )
    (net (code "69") (name "unconnected-(STM32F103C8T6-PA3-Pad13)") (class "Default")
      (node (ref "STM32F103C8T6") (pin "13") (pinfunction "PA3_13") (pintype "passive"))
    )
    (net (code "70") (name "unconnected-(STM32F103C8T6-PA4-Pad14)") (class "Default")
      (node (ref "STM32F103C8T6") (pin "14") (pinfunction "PA4_14") (pintype "passive"))
    )
    (net (code "71") (name "unconnected-(STM32F103C8T6-PA5-Pad15)") (class "Default")
      (node (ref "STM32F103C8T6") (pin "15") (pinfunction "PA5_15") (pintype "passive"))
    )
    (net (code "72") (name "unconnected-(STM32F103C8T6-PA6-Pad16)") (class "Default")
      (node (ref "STM32F103C8T6") (pin "16") (pinfunction "PA6_16") (pintype "passive"))
    )
    (net (code "73") (name "unconnected-(STM32F103C8T6-PA7-Pad17)") (class "Default")
      (node (ref "STM32F103C8T6") (pin "17") (pinfunction "PA7_17") (pintype "passive"))
    )
    (net (code "74") (name "unconnected-(STM32F103C8T6-PA8-Pad29)") (class "Default")
      (node (ref "STM32F103C8T6") (pin "29") (pinfunction "PA8_29") (pintype "passive"))
    )
    (net (code "75") (name "unconnected-(STM32F103C8T6-PA9-Pad30)") (class "Default")
      (node (ref "STM32F103C8T6") (pin "30") (pinfunction "PA9_30") (pintype "passive"))
    )
    (net (code "76") (name "unconnected-(STM32F103C8T6-PA12-Pad33)") (class "Default")
      (node (ref "STM32F103C8T6") (pin "33") (pinfunction "PA12_33") (pintype "passive"))
    )
    (net (code "77") (name "unconnected-(STM32F103C8T6-PA13-Pad34)") (class "Default")
      (node (ref "STM32F103C8T6") (pin "34") (pinfunction "PA13_34") (pintype "passive"))
    )
    (net (code "78") (name "unconnected-(STM32F103C8T6-PA14-Pad37)") (class "Default")
      (node (ref "STM32F103C8T6") (pin "37") (pinfunction "PA14_37") (pintype "passive"))
    )
    (net (code "79") (name "unconnected-(STM32F103C8T6-PB0-Pad18)") (class "Default")
      (node (ref "STM32F103C8T6") (pin "18") (pinfunction "PB0_18") (pintype "passive"))
    )
    (net (code "80") (name "unconnected-(STM32F103C8T6-PB1-Pad19)") (class "Default")
      (node (ref "STM32F103C8T6") (pin "19") (pinfunction "PB1_19") (pintype "passive"))
    )
    (net (code "81") (name "unconnected-(STM32F103C8T6-PB2-Pad20)") (class "Default")
      (node (ref "STM32F103C8T6") (pin "20") (pinfunction "PB2_20") (pintype "passive"))
    )
    (net (code "82") (name "unconnected-(STM32F103C8T6-PB3-Pad39)") (class "Default")
      (node (ref "STM32F103C8T6") (pin "39") (pinfunction "PB3_39") (pintype "passive"))
    )
    (net (code "83") (name "unconnected-(STM32F103C8T6-PB4-Pad40)") (class "Default")
      (node (ref "STM32F103C8T6") (pin "40") (pinfunction "PB4_40") (pintype "passive"))
    )
    (net (code "84") (name "unconnected-(STM32F103C8T6-PB5-Pad41)") (class "Default")
      (node (ref "STM32F103C8T6") (pin "41") (pinfunction "PB5_41") (pintype "passive"))
    )
    (net (code "85") (name "unconnected-(STM32F103C8T6-PB6-Pad42)") (class "Default")
      (node (ref "STM32F103C8T6") (pin "42") (pinfunction "PB6_42") (pintype "passive"))
    )
    (net (code "86") (name "unconnected-(STM32F103C8T6-PB7-Pad43)") (class "Default")
      (node (ref "STM32F103C8T6") (pin "43") (pinfunction "PB7_43") (pintype "passive"))
    )
    (net (code "87") (name "unconnected-(STM32F103C8T6-PB8-Pad45)") (class "Default")
      (node (ref "STM32F103C8T6") (pin "45") (pinfunction "PB8_45") (pintype "passive"))
    )
    (net (code "88") (name "unconnected-(STM32F103C8T6-PB9-Pad46)") (class "Default")
      (node (ref "STM32F103C8T6") (pin "46") (pinfunction "PB9_46") (pintype "passive"))
    )
    (net (code "89") (name "unconnected-(STM32F103C8T6-PB12-Pad25)") (class "Default")
      (node (ref "STM32F103C8T6") (pin "25") (pinfunction "PB12_25") (pintype "passive"))
    )
    (net (code "90") (name "unconnected-(STM32F103C8T6-PB13-Pad26)") (class "Default")
      (node (ref "STM32F103C8T6") (pin "26") (pinfunction "PB13_26") (pintype "passive"))
    )
    (net (code "91") (name "unconnected-(STM32F103C8T6-PB15-Pad28)") (class "Default")
      (node (ref "STM32F103C8T6") (pin "28") (pinfunction "PB15_28") (pintype "passive"))
    )
    (net (code "92") (name "unconnected-(STM32F103C8T6-PC14-OSC32_IN-Pad3)") (class "Default")
      (node (ref "STM32F103C8T6") (pin "3") (pinfunction "PC14-OSC32_IN_3") (pintype "passive"))
    )
    (net (code "93") (name "unconnected-(STM32F103C8T6-PC15-OSC32_OUT-Pad4)") (class "Default")
      (node (ref "STM32F103C8T6") (pin "4") (pinfunction "PC15-OSC32_OUT_4") (pintype "passive"))
    )
    (net (code "94") (name "unconnected-(U1-ADJ-Pad5)") (class "Default")
      (node (ref "U1") (pin "5") (pinfunction "ADJ_5") (pintype "input"))
    )
    (net (code "95") (name "unconnected-(U1-TAB-Pad6)") (class "Default")
      (node (ref "U1") (pin "6") (pinfunction "TAB_6") (pintype "passive"))
    )
    (net (code "96") (name "unconnected-(U2-NC-Pad7)") (class "Default")
      (node (ref "U2") (pin "7") (pinfunction "NC_7") (pintype "passive"))
    )
  )
)
